# 1_SLOT_PCB.net
KiCad netlist of a schematic drawn in Altium Designer
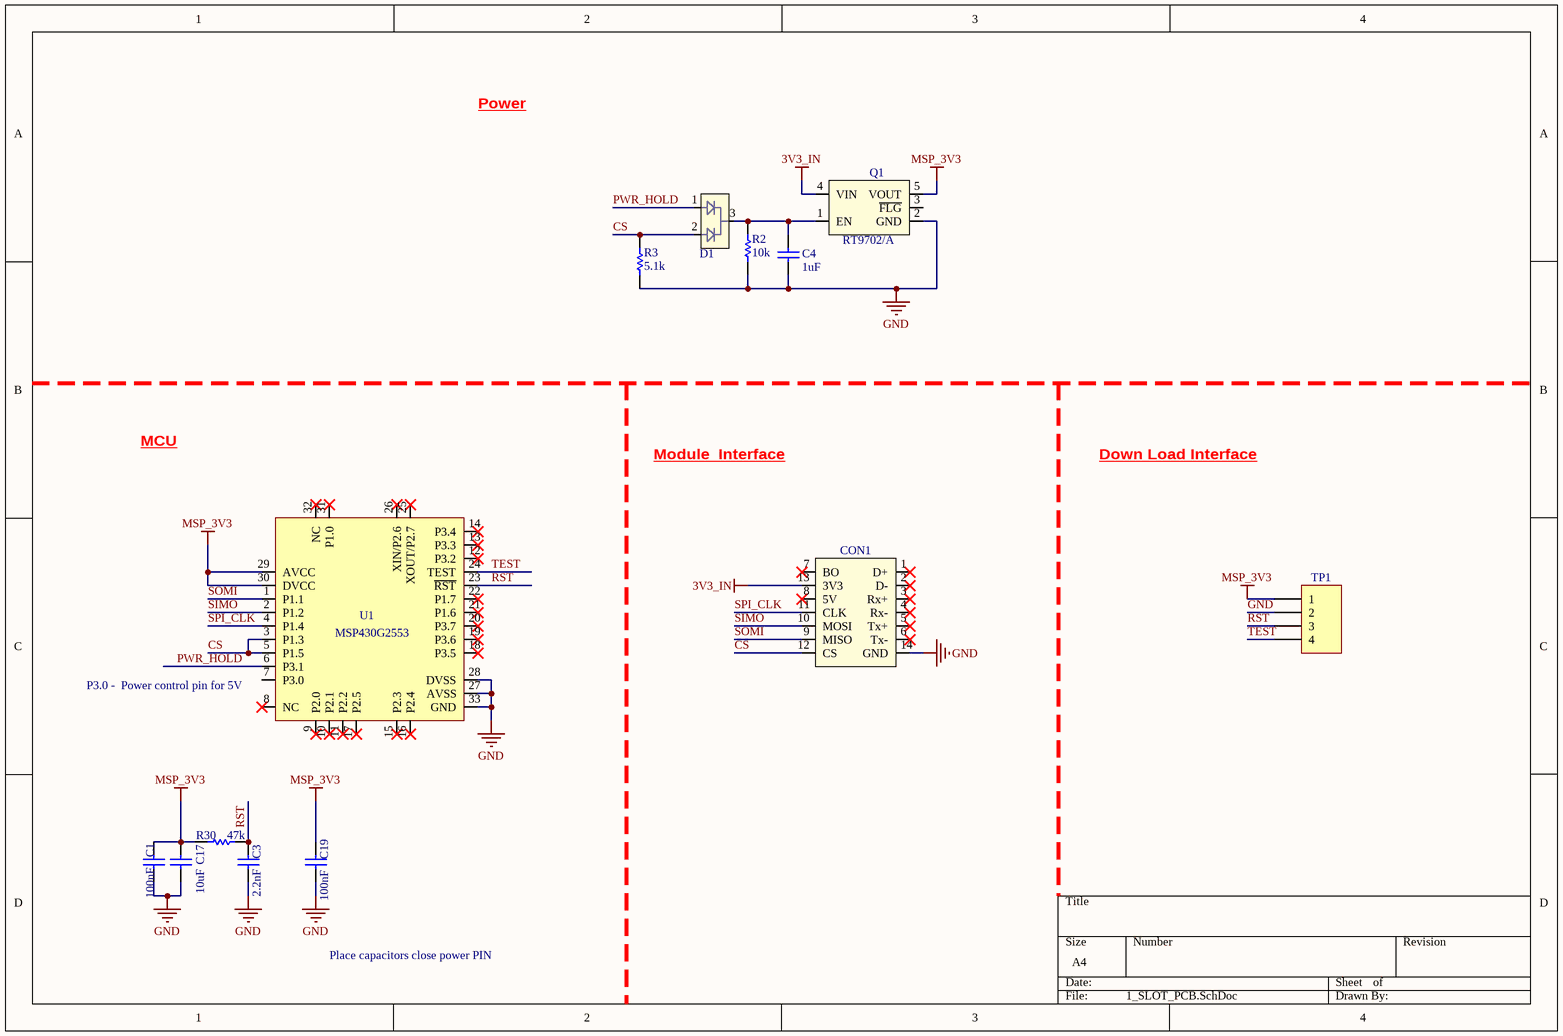
[diagram p0: 1_SLOT_PCB.SchDoc]

(export (version "E")
  (design (tool "Eeschema 10.0.6"))
  (components
    (comp (ref "C1")
      (value "100nF")
      (footprint "0402")
      (description "Capacitor")
      (fields (field (name "Comment") "Cap") (field (name "PUBLISHER") "Altium Limited"))
      (libsource (lib "Miscellaneous Devices") (part "Cap"))
    )
    (comp (ref "C3")
      (value "2.2nF")
      (footprint "0402")
      (description "Capacitor")
      (fields (field (name "Comment") "Cap") (field (name "PUBLISHER") "Altium Limited"))
      (libsource (lib "Miscellaneous Devices") (part "Cap"))
    )
    (comp (ref "C4")
      (value "1uF")
      (footprint "0402")
      (description "Capacitor")
      (fields (field (name "Comment") "Cap") (field (name "PUBLISHER") "Altium Limited"))
      (libsource (lib "Miscellaneous Devices") (part "Cap"))
    )
    (comp (ref "C17")
      (value "10uF")
      (footprint "0603")
      (description "Capacitor")
      (fields (field (name "Comment") "Cap") (field (name "PUBLISHER") "Altium Limited"))
      (libsource (lib "Miscellaneous Devices") (part "Cap"))
    )
    (comp (ref "C19")
      (value "100nF")
      (footprint "0402")
      (description "Capacitor")
      (fields (field (name "Comment") "Cap") (field (name "PUBLISHER") "Altium Limited"))
      (libsource (lib "Miscellaneous Devices") (part "Cap"))
    )
    (comp (ref "CON1")
      (value "~")
      (footprint "edge-connector-0.8*1.0")
      (description "Module interface")
      (libsource (lib "Connector") (part "NP_EdgeConnector-2*7"))
    )
    (comp (ref "D1")
      (value "Dual Diode (common cath)")
      (footprint "SOT-523")
      (description "BAS40-05T")
      (fields (field (name "MANUFACTURER") "DIODES") (field (name "PART NUMBER") "BAS40-05T-7-F"))
      (libsource (lib "Discrete") (part "Dual Diode (common cath)"))
    )
    (comp (ref "Q1")
      (value "RT9702/A")
      (footprint "SOT-23-5")
      (description "RICHTEK RT9702/A")
      (fields (field (name "MANUFACTURER") "RICHTEK") (field (name "PART NUMBER") "RT9702/A GB"))
      (libsource (lib "Discrete") (part "RT9702/A"))
    )
    (comp (ref "R2")
      (value "10k")
      (footprint "0402")
      (description "Resistor")
      (fields (field (name "Comment") "Res1") (field (name "PUBLISHER") "Altium Limited"))
      (libsource (lib "Miscellaneous Devices") (part "Res1"))
    )
    (comp (ref "R3")
      (value "5.1k")
      (footprint "0402")
      (description "Resistor")
      (fields (field (name "Comment") "Res1") (field (name "PUBLISHER") "Altium Limited"))
      (libsource (lib "Miscellaneous Devices") (part "Res1"))
    )
    (comp (ref "R30")
      (value "47k")
      (footprint "0402")
      (description "Resistor")
      (fields (field (name "Comment") "Res1") (field (name "PUBLISHER") "Altium Limited"))
      (libsource (lib "Miscellaneous Devices") (part "Res1"))
    )
    (comp (ref "TP1")
      (value "~")
      (footprint "header 4x1 30*30-55mil")
      (description "Down Load Interface")
      (fields (field (name "PUBLISHER") "Altium Limited"))
      (libsource (lib "Miscellaneous Connectors") (part "Header 4"))
    )
    (comp (ref "U1")
      (value "MSP430G2553")
      (footprint "QFN-32-5x5")
      (fields (field (name "MANUFACTURER") "TI") (field (name "PART NUMBER") "MSP430G2353IRHB32R"))
      (libsource (lib "IC") (part "MSP430G2553"))
    )
  )
  (nets
    (net (code "1") (name "/CS") (class "Default")
      (node (ref "CON1") (pin "12") (pinfunction "CS_12") (pintype "passive"))
      (node (ref "D1") (pin "2") (pinfunction "2_2") (pintype "passive"))
      (node (ref "R3") (pin "1") (pinfunction "1_1") (pintype "passive"))
      (node (ref "U1") (pin "3") (pinfunction "P1.3_3") (pintype "passive"))
      (node (ref "U1") (pin "5") (pinfunction "P1.5_5") (pintype "passive"))
    )
    (net (code "2") (name "/PWR_HOLD") (class "Default")
      (node (ref "D1") (pin "1") (pinfunction "1_1") (pintype "passive"))
      (node (ref "U1") (pin "6") (pinfunction "P3.1_6") (pintype "passive"))
    )
    (net (code "3") (name "/RST") (class "Default")
      (node (ref "C3") (pin "2") (pinfunction "2_2") (pintype "passive"))
      (node (ref "R30") (pin "1") (pinfunction "1_1") (pintype "passive"))
      (node (ref "TP1") (pin "3") (pinfunction "3_3") (pintype "passive"))
      (node (ref "U1") (pin "23") (pinfunction "~{RST}_23") (pintype "passive"))
    )
    (net (code "4") (name "/SIMO") (class "Default")
      (node (ref "CON1") (pin "10") (pinfunction "MOSI_10") (pintype "passive"))
      (node (ref "U1") (pin "2") (pinfunction "P1.2_2") (pintype "passive"))
    )
    (net (code "5") (name "/SOMI") (class "Default")
      (node (ref "CON1") (pin "9") (pinfunction "MISO_9") (pintype "passive"))
      (node (ref "U1") (pin "1") (pinfunction "P1.1_1") (pintype "passive"))
    )
    (net (code "6") (name "/SPI_CLK") (class "Default")
      (node (ref "CON1") (pin "11") (pinfunction "CLK_11") (pintype "passive"))
      (node (ref "U1") (pin "4") (pinfunction "P1.4_4") (pintype "passive"))
    )
    (net (code "7") (name "/TEST") (class "Default")
      (node (ref "TP1") (pin "4") (pinfunction "4_4") (pintype "passive"))
      (node (ref "U1") (pin "24") (pinfunction "TEST_24") (pintype "passive"))
    )
    (net (code "8") (name "3V3_IN") (class "Default")
      (node (ref "CON1") (pin "13") (pinfunction "3V3_13") (pintype "passive"))
      (node (ref "Q1") (pin "4") (pinfunction "VIN_4") (pintype "passive"))
    )
    (net (code "9") (name "GND") (class "Default")
      (node (ref "C1") (pin "1") (pinfunction "1_1") (pintype "passive"))
      (node (ref "C17") (pin "1") (pinfunction "1_1") (pintype "passive"))
      (node (ref "C19") (pin "1") (pinfunction "1_1") (pintype "passive"))
      (node (ref "C3") (pin "1") (pinfunction "1_1") (pintype "passive"))
      (node (ref "C4") (pin "1") (pinfunction "1_1") (pintype "passive"))
      (node (ref "CON1") (pin "14") (pinfunction "GND_14") (pintype "passive"))
      (node (ref "Q1") (pin "2") (pinfunction "GND_2") (pintype "passive"))
      (node (ref "R2") (pin "2") (pinfunction "2_2") (pintype "passive"))
      (node (ref "R3") (pin "2") (pinfunction "2_2") (pintype "passive"))
      (node (ref "TP1") (pin "2") (pinfunction "2_2") (pintype "passive"))
      (node (ref "U1") (pin "27") (pinfunction "AVSS_27") (pintype "passive"))
      (node (ref "U1") (pin "28") (pinfunction "DVSS_28") (pintype "passive"))
      (node (ref "U1") (pin "33") (pinfunction "GND_33") (pintype "passive"))
    )
    (net (code "10") (name "MSP_3V3") (class "Default")
      (node (ref "C1") (pin "2") (pinfunction "2_2") (pintype "passive"))
      (node (ref "C17") (pin "2") (pinfunction "2_2") (pintype "passive"))
      (node (ref "C19") (pin "2") (pinfunction "2_2") (pintype "passive"))
      (node (ref "Q1") (pin "5") (pinfunction "VOUT_5") (pintype "passive"))
      (node (ref "R30") (pin "2") (pinfunction "2_2") (pintype "passive"))
      (node (ref "TP1") (pin "1") (pinfunction "1_1") (pintype "passive"))
      (node (ref "U1") (pin "29") (pinfunction "AVCC_29") (pintype "passive"))
      (node (ref "U1") (pin "30") (pinfunction "DVCC_30") (pintype "passive"))
    )
    (net (code "11") (name "Net-(Q1-EN)") (class "Default")
      (node (ref "C4") (pin "2") (pinfunction "2_2") (pintype "passive"))
      (node (ref "D1") (pin "3") (pinfunction "3_3") (pintype "passive"))
      (node (ref "Q1") (pin "1") (pinfunction "EN_1") (pintype "passive"))
      (node (ref "R2") (pin "1") (pinfunction "1_1") (pintype "passive"))
    )
    (net (code "12") (name "unconnected-(CON1-5V-Pad8)") (class "Default")
      (node (ref "CON1") (pin "8") (pinfunction "5V_8") (pintype "passive+no_connect"))
    )
    (net (code "13") (name "unconnected-(CON1-BO-Pad7)") (class "Default")
      (node (ref "CON1") (pin "7") (pinfunction "BO_7") (pintype "passive+no_connect"))
    )
    (net (code "14") (name "unconnected-(CON1-D+-Pad1)") (class "Default")
      (node (ref "CON1") (pin "1") (pinfunction "D+_1") (pintype "passive+no_connect"))
    )
    (net (code "15") (name "unconnected-(CON1-D--Pad2)") (class "Default")
      (node (ref "CON1") (pin "2") (pinfunction "D-_2") (pintype "passive+no_connect"))
    )
    (net (code "16") (name "unconnected-(CON1-Rx+-Pad3)") (class "Default")
      (node (ref "CON1") (pin "3") (pinfunction "Rx+_3") (pintype "passive+no_connect"))
    )
    (net (code "17") (name "unconnected-(CON1-Rx--Pad4)") (class "Default")
      (node (ref "CON1") (pin "4") (pinfunction "Rx-_4") (pintype "passive+no_connect"))
    )
    (net (code "18") (name "unconnected-(CON1-Tx+-Pad5)") (class "Default")
      (node (ref "CON1") (pin "5") (pinfunction "Tx+_5") (pintype "passive+no_connect"))
    )
    (net (code "19") (name "unconnected-(CON1-Tx--Pad6)") (class "Default")
      (node (ref "CON1") (pin "6") (pinfunction "Tx-_6") (pintype "passive+no_connect"))
    )
    (net (code "20") (name "unconnected-(Q1-~{FLG}-Pad3)") (class "Default")
      (node (ref "Q1") (pin "3") (pinfunction "~{FLG}_3") (pintype "passive"))
    )
    (net (code "21") (name "unconnected-(U1-NC-Pad8)") (class "Default")
      (node (ref "U1") (pin "8") (pinfunction "NC_8") (pintype "passive+no_connect"))
    )
    (net (code "22") (name "unconnected-(U1-NC-Pad32)") (class "Default")
      (node (ref "U1") (pin "32") (pinfunction "NC_32") (pintype "passive+no_connect"))
    )
    (net (code "23") (name "unconnected-(U1-P1.0-Pad31)") (class "Default")
      (node (ref "U1") (pin "31") (pinfunction "P1.0_31") (pintype "passive+no_connect"))
    )
    (net (code "24") (name "unconnected-(U1-P1.6-Pad21)") (class "Default")
      (node (ref "U1") (pin "21") (pinfunction "P1.6_21") (pintype "passive+no_connect"))
    )
    (net (code "25") (name "unconnected-(U1-P1.7-Pad22)") (class "Default")
      (node (ref "U1") (pin "22") (pinfunction "P1.7_22") (pintype "passive+no_connect"))
    )
    (net (code "26") (name "unconnected-(U1-P2.0-Pad9)") (class "Default")
      (node (ref "U1") (pin "9") (pinfunction "P2.0_9") (pintype "passive+no_connect"))
    )
    (net (code "27") (name "unconnected-(U1-P2.1-Pad10)") (class "Default")
      (node (ref "U1") (pin "10") (pinfunction "P2.1_10") (pintype "passive+no_connect"))
    )
    (net (code "28") (name "unconnected-(U1-P2.2-Pad11)") (class "Default")
      (node (ref "U1") (pin "11") (pinfunction "P2.2_11") (pintype "passive+no_connect"))
    )
    (net (code "29") (name "unconnected-(U1-P2.3-Pad15)") (class "Default")
      (node (ref "U1") (pin "15") (pinfunction "P2.3_15") (pintype "passive+no_connect"))
    )
    (net (code "30") (name "unconnected-(U1-P2.4-Pad16)") (class "Default")
      (node (ref "U1") (pin "16") (pinfunction "P2.4_16") (pintype "passive+no_connect"))
    )
    (net (code "31") (name "unconnected-(U1-P2.5-Pad17)") (class "Default")
      (node (ref "U1") (pin "17") (pinfunction "P2.5_17") (pintype "passive+no_connect"))
    )
    (net (code "32") (name "unconnected-(U1-P3.0-Pad7)") (class "Default")
      (node (ref "U1") (pin "7") (pinfunction "P3.0_7") (pintype "passive"))
    )
    (net (code "33") (name "unconnected-(U1-P3.2-Pad12)") (class "Default")
      (node (ref "U1") (pin "12") (pinfunction "P3.2_12") (pintype "passive+no_connect"))
    )
    (net (code "34") (name "unconnected-(U1-P3.3-Pad13)") (class "Default")
      (node (ref "U1") (pin "13") (pinfunction "P3.3_13") (pintype "passive+no_connect"))
    )
    (net (code "35") (name "unconnected-(U1-P3.4-Pad14)") (class "Default")
      (node (ref "U1") (pin "14") (pinfunction "P3.4_14") (pintype "passive+no_connect"))
    )
    (net (code "36") (name "unconnected-(U1-P3.5-Pad18)") (class "Default")
      (node (ref "U1") (pin "18") (pinfunction "P3.5_18") (pintype "passive+no_connect"))
    )
    (net (code "37") (name "unconnected-(U1-P3.6-Pad19)") (class "Default")
      (node (ref "U1") (pin "19") (pinfunction "P3.6_19") (pintype "passive+no_connect"))
    )
    (net (code "38") (name "unconnected-(U1-P3.7-Pad20)") (class "Default")
      (node (ref "U1") (pin "20") (pinfunction "P3.7_20") (pintype "passive+no_connect"))
    )
    (net (code "39") (name "unconnected-(U1-XIN{slash}P2.6-Pad26)") (class "Default")
      (node (ref "U1") (pin "26") (pinfunction "XIN/P2.6_26") (pintype "passive+no_connect"))
    )
    (net (code "40") (name "unconnected-(U1-XOUT{slash}P2.7-Pad25)") (class "Default")
      (node (ref "U1") (pin "25") (pinfunction "XOUT/P2.7_25") (pintype "passive+no_connect"))
    )
  )
)
